# EN1190_EDP_Semester_2_Schematic.net
KiCad netlist of a schematic drawn in Altium Designer
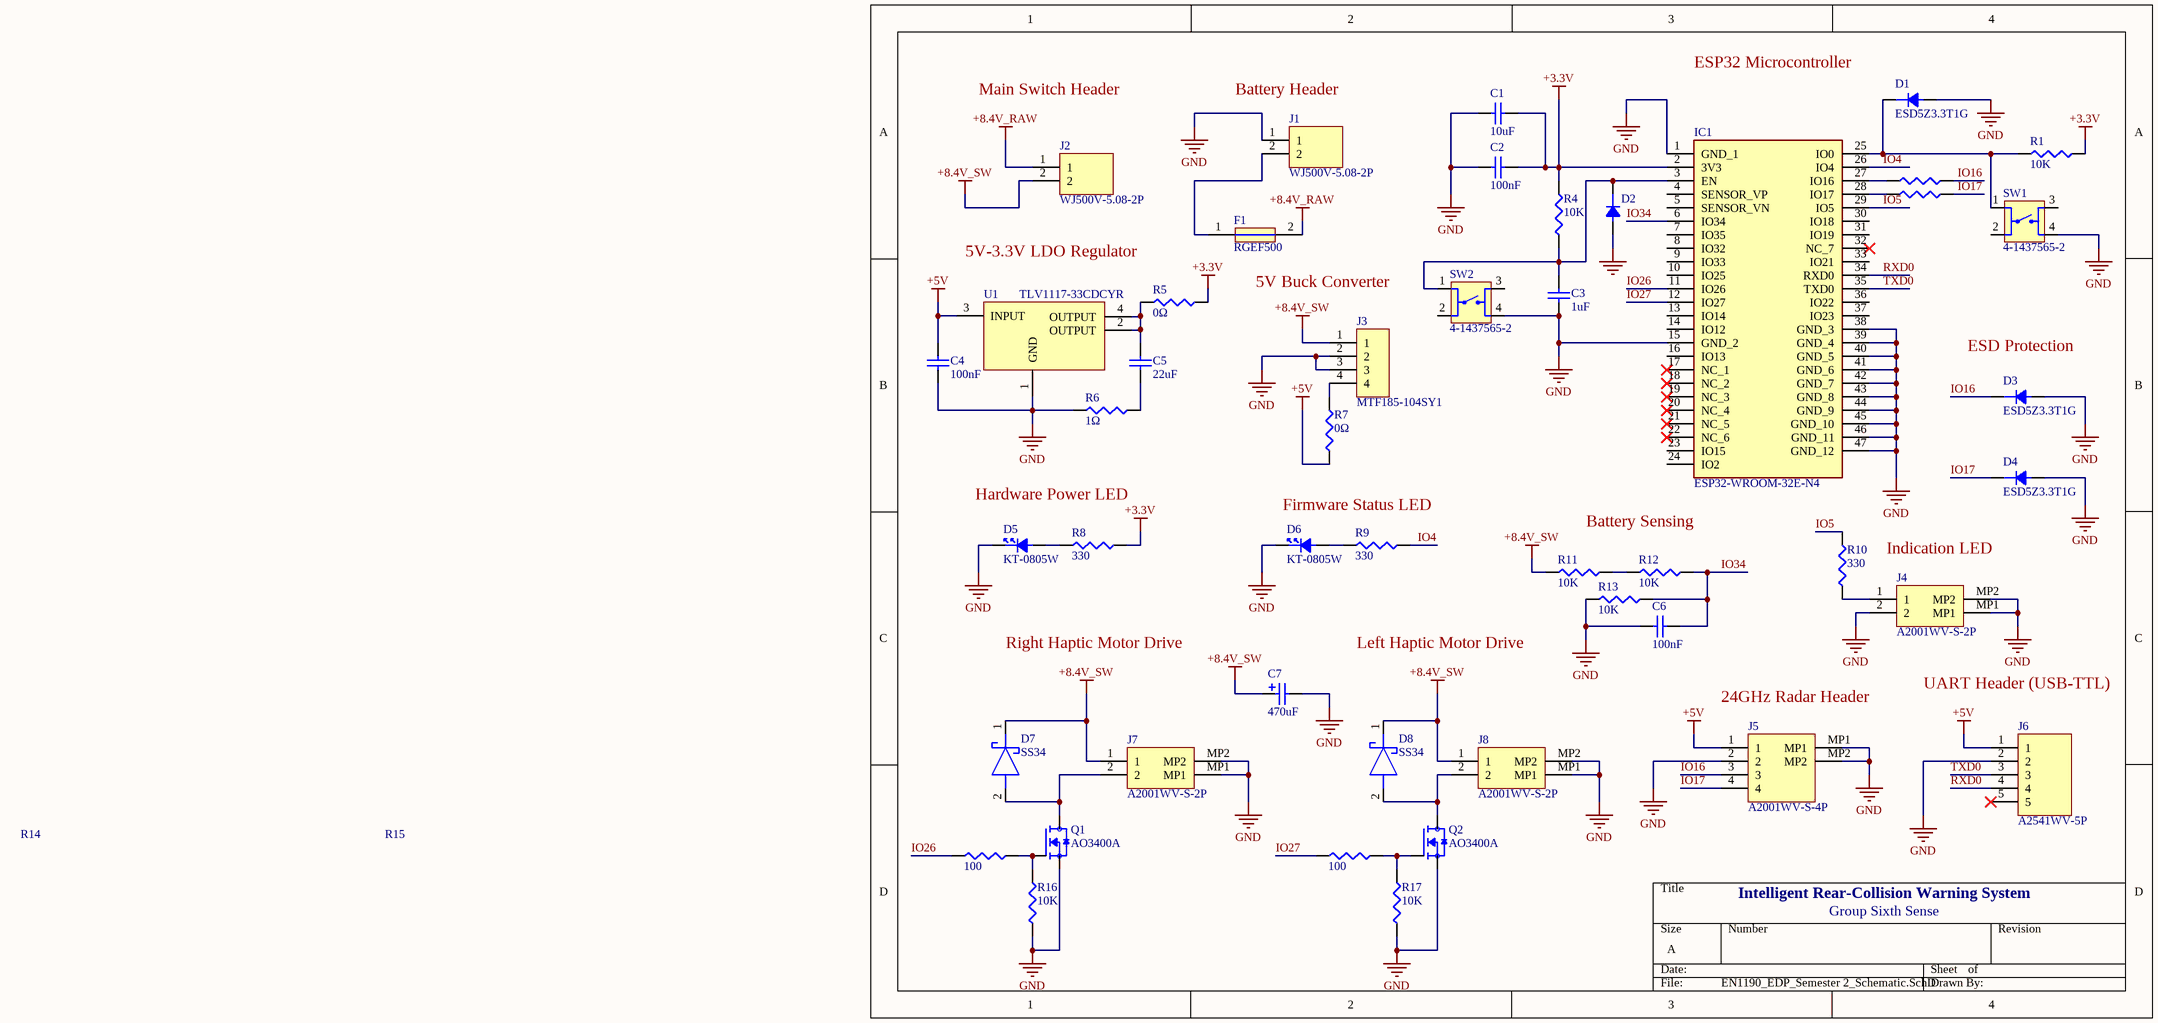
[diagram p0: EN1190_EDP_Semester 2_Schematic.SchDoc]

(export (version "E")
  (design (tool "Eeschema 10.0.6"))
  (components
    (comp (ref "C1")
      (value "10uF")
      (footprint "CAPC2012X145N")
      (description "10uF ±10% 25V Ceramic Capacitor X5R 0805")
      (fields
        (field (name "LCSC PART NUMBER") "C15850")
        (field (name "MANUFACTURER") "Samsung Electro-Mechanics")
      )
      (libsource (lib "Integrated_Library1") (part "CL21A106KAYNNNE"))
    )
    (comp (ref "C2")
      (value "100nF")
      (footprint "CAPC2012X70")
      (description "100nF ±10% 50V Ceramic Capacitor X7R 0805")
      (fields
        (field (name "MANUFACTURER") "YAGEO")
        (field (name "MANUFACTURER PART NUMBER") "CC0805KRX7R9BB104")
      )
      (libsource (lib "Integrated_Library1") (part "CC0805KRX7R9BB104"))
    )
    (comp (ref "C3")
      (value "1uF")
      (footprint "CAPC2012X135N")
      (description "1uF ±10% 50V Ceramic Capacitor X7R 0805")
      (fields
        (field (name "LCSC PART NUMBER") "C28323")
        (field (name "MANUFACTUER PART NUMBER") "CL21B105KBFNNNE")
      )
      (libsource (lib "Integrated_Library1") (part "CL21B105KBFNNNE"))
    )
    (comp (ref "C4")
      (value "100nF")
      (footprint "CAPC2012X70")
      (description "100nF ±10% 50V Ceramic Capacitor X7R 0805")
      (fields
        (field (name "MANUFACTURER") "YAGEO")
        (field (name "MANUFACTURER PART NUMBER") "CC0805KRX7R9BB104")
      )
      (libsource (lib "Integrated_Library1") (part "CC0805KRX7R9BB104"))
    )
    (comp (ref "C5")
      (value "22uF")
      (footprint "CAPC3216X180N")
      (description "22uF ±10% 16V Ceramic Capacitor X5R 1206")
      (fields (field (name "LCSC PART NUMBER") "C90146"))
      (libsource (lib "Integrated_Library1") (part "CL31A226KOHNNNE"))
    )
    (comp (ref "C6")
      (value "100nF")
      (footprint "CAPC2012X70")
      (description "100nF ±10% 50V Ceramic Capacitor X7R 0805")
      (fields
        (field (name "MANUFACTURER") "YAGEO")
        (field (name "MANUFACTURER PART NUMBER") "CC0805KRX7R9BB104")
      )
      (libsource (lib "Integrated_Library1") (part "CC0805KRX7R9BB104"))
    )
    (comp (ref "C7")
      (value "470uF")
      (footprint "CAPPRD500W60D1025H1400")
      (description "470uF 25V Aluminum Electrolytic Capacitors Through Hole,D10xL12.5mm 10000hrs@105℃")
      (fields (field (name "LCSC PART NUMBER") "C88740") (field (name "MANUFACTURER") "Rubycon"))
      (libsource (lib "Integrated_Library1") (part "25YXJ470M10X12.5"))
    )
    (comp (ref "D1")
      (value "ESD5Z3.3T1G")
      (footprint "SODFL1608X70N")
      (description "14.1VC Clamp 11.2A Ipp TVS DIODE SOD-523")
      (fields (field (name "MANUFACTURER") "onsemi") (field (name "LCSC PART NUMBER") "C61148"))
      (libsource (lib "Integrated_Library1") (part "ESD5Z3.3T1G"))
    )
    (comp (ref "D2")
      (value "ESD5Z3.3T1G")
      (footprint "SODFL1608X70N")
      (description "14.1VC Clamp 11.2A Ipp TVS DIODE SOD-523")
      (fields (field (name "MANUFACTURER") "onsemi") (field (name "LCSC PART NUMBER") "C61148"))
      (libsource (lib "Integrated_Library1") (part "ESD5Z3.3T1G"))
    )
    (comp (ref "D3")
      (value "ESD5Z3.3T1G")
      (footprint "SODFL1608X70N")
      (description "14.1VC Clamp 11.2A Ipp TVS DIODE SOD-523")
      (fields (field (name "MANUFACTURER") "onsemi") (field (name "LCSC PART NUMBER") "C61148"))
      (libsource (lib "Integrated_Library1") (part "ESD5Z3.3T1G"))
    )
    (comp (ref "D4")
      (value "ESD5Z3.3T1G")
      (footprint "SODFL1608X70N")
      (description "14.1VC Clamp 11.2A Ipp TVS DIODE SOD-523")
      (fields (field (name "MANUFACTURER") "onsemi") (field (name "LCSC PART NUMBER") "C61148"))
      (libsource (lib "Integrated_Library1") (part "ESD5Z3.3T1G"))
    )
    (comp (ref "D5")
      (value "KT-0805W")
      (footprint "LED_KT-0805W")
      (description "White LED Indication - Discrete 2.6V~3.2V 0805")
      (fields (field (name "MANUFACTURER") "Hubei KENTO Elec") (field (name "LCSC PART NUMBER") "C34499"))
      (libsource (lib "Integrated_Library1") (part "KT-0805W"))
    )
    (comp (ref "D6")
      (value "KT-0805W")
      (footprint "LED_KT-0805W")
      (description "White LED Indication - Discrete 2.6V~3.2V 0805")
      (fields (field (name "MANUFACTURER") "Hubei KENTO Elec") (field (name "LCSC PART NUMBER") "C34499"))
      (libsource (lib "Integrated_Library1") (part "KT-0805W"))
    )
    (comp (ref "D7")
      (value "SS34")
      (footprint "DIOM5127X241N")
      (description "Diode Independent 40V 3A Surface Mount SMA(DO-214AC)")
      (fields
        (field (name "LCSC PART NUMBER") "C8678")
        (field (name "MANUFACTURER") "MDD(Microdiode Semiconductor)")
      )
      (libsource (lib "Integrated_Library1") (part "SS34 SMA"))
    )
    (comp (ref "D8")
      (value "SS34")
      (footprint "DIOM5127X241N")
      (description "Diode Independent 40V 3A Surface Mount SMA(DO-214AC)")
      (fields
        (field (name "LCSC PART NUMBER") "C8678")
        (field (name "MANUFACTURER") "MDD(Microdiode Semiconductor)")
      )
      (libsource (lib "Integrated_Library1") (part "SS34 SMA"))
    )
    (comp (ref "F1")
      (value "RGEF500")
      (footprint "RGEF500")
      (description "Polymeric PTC Resettable Fuse 16V 5A Through Hole P=5.08mm")
      (fields (field (name "MANUFACTURER") "Littelfuse") (field (name "LCSC PART NUMBER") "C468988"))
      (libsource (lib "Integrated_Library1") (part "RGEF500"))
    )
    (comp (ref "IC1")
      (value "ESP32-WROOM-32E-N4")
      (footprint "ESP32WROOM32EN4")
      (description "2.4GHz On-board PCB Antenna -98dBm SMD,25.5x18mm RF Transceiver Modules and Modems RoHS")
      (fields
        (field (name "MOUSER PART NUMBER") "356-ESP32WRM32E132PH")
        (field (name "LCSC PART NUMBER") "C701341")
      )
      (libsource (lib "Schlib3") (part "ESP32-WROOM-32E-N4"))
    )
    (comp (ref "J1")
      (value "WJ500V-5.08-2P")
      (footprint "WJ500V5082P")
      (description "2 Position Wire to Board Terminal Block Through Hole 5.08mm")
      (fields (field (name "LCSC PART NUMBER") "C8465"))
      (libsource (lib "Schlib3") (part "WJ500V-5.08-2P"))
    )
    (comp (ref "J2")
      (value "WJ500V-5.08-2P")
      (footprint "WJ500V5082P")
      (description "2 Position Wire to Board Terminal Block Through Hole 5.08mm")
      (fields (field (name "LCSC PART NUMBER") "C8465"))
      (libsource (lib "Schlib3") (part "WJ500V-5.08-2P"))
    )
    (comp (ref "J3")
      (value "MTF185-104SY1")
      (footprint "RHDR4W64P0X254_1X4_1041X250X865P")
      (description "Female Header 4 Position 2.54mm Pitch Single Row Through Hole")
      (fields (field (name "LCSC PART NUMBER") "C358718") (field (name "MANUFACTURER") "Mintron"))
      (libsource (lib "Integrated_Library1") (part "MTF185-104SY1"))
    )
    (comp (ref "J4")
      (value "A2001WV-S-2P")
      (footprint "A2001WVS2P")
      (description "Connector Header 2 position 2mm Pitch")
      (fields (field (name "LCSC PART NUMBER") "C225226"))
      (libsource (lib "Integrated_Library1") (part "A2001WV-S-2P"))
    )
    (comp (ref "J5")
      (value "A2001WV-S-4P")
      (footprint "A2001WVS4P")
      (description "Connector Header 4 position 2mm Pitch")
      (fields (field (name "LCSC PART NUMBER") "C225228"))
      (libsource (lib "Integrated_Library1") (part "A2001WV-S-4P"))
    )
    (comp (ref "J6")
      (value "A2541WV-5P")
      (footprint "HDRV5W64P0X254_1X5_1270X254X899P")
      (description "Pin Header 5 Position 2.54mm Pitch Single Row Through Hole -40℃~+105℃")
      (fields (field (name "LCSC PART NUMBER") "C225480"))
      (libsource (lib "Integrated_Library1") (part "A2541WV-5P"))
    )
    (comp (ref "J7")
      (value "A2001WV-S-2P")
      (footprint "A2001WVS2P")
      (description "Connector Header 2 position 2mm Pitch")
      (fields (field (name "LCSC PART NUMBER") "C225226"))
      (libsource (lib "Integrated_Library1") (part "A2001WV-S-2P"))
    )
    (comp (ref "J8")
      (value "A2001WV-S-2P")
      (footprint "A2001WVS2P")
      (description "Connector Header 2 position 2mm Pitch")
      (fields (field (name "LCSC PART NUMBER") "C225226"))
      (libsource (lib "Integrated_Library1") (part "A2001WV-S-2P"))
    )
    (comp (ref "Q1")
      (value "AO3400A")
      (footprint "SOT95P280X125-3N")
      (description "N-Channel 30 V 5.7A (Ta) 1.4W (Ta) Surface Mount SOT-23-3")
      (fields (field (name "MF") "Alpha & Omega Semiconductor") (field (name "LCSC PART NUMBER") "C20917"))
      (libsource (lib "Integrated_Library1") (part "AO3400A"))
    )
    (comp (ref "Q2")
      (value "AO3400A")
      (footprint "SOT95P280X125-3N")
      (description "N-Channel 30 V 5.7A (Ta) 1.4W (Ta) Surface Mount SOT-23-3")
      (fields (field (name "MF") "Alpha & Omega Semiconductor") (field (name "LCSC PART NUMBER") "C20917"))
      (libsource (lib "Integrated_Library1") (part "AO3400A"))
    )
    (comp (ref "R1")
      (value "10K")
      (footprint "RESC2012X65N")
      (description "10kΩ ±1% 125mW 0805 Thick Film Resistor")
      (fields
        (field (name "LCSC PART NUMBER") "C17414")
        (field (name "MANUFACTUER PART NUMBER") "0805W8F1002T5E")
      )
      (libsource (lib "Integrated_Library1") (part "0805W8F1002T5E"))
    )
    (comp (ref "R2")
      (value "0Ω")
      (footprint "RESC2012X65N")
      (description "0Ω ±1% 125mW 0805 Thick Film Resistor")
      (fields
        (field (name "MANUFACTURER") "UNI-ROYAL")
        (field (name "MANUFACTURER PART NUMBER") "0805W8F0000T5E")
      )
      (libsource (lib "Integrated_Library1") (part "0805W8F0000T5E"))
    )
    (comp (ref "R3")
      (value "0Ω")
      (footprint "RESC2012X65N")
      (description "0Ω ±1% 125mW 0805 Thick Film Resistor")
      (fields
        (field (name "MANUFACTURER") "UNI-ROYAL")
        (field (name "MANUFACTURER PART NUMBER") "0805W8F0000T5E")
      )
      (libsource (lib "Integrated_Library1") (part "0805W8F0000T5E"))
    )
    (comp (ref "R4")
      (value "10K")
      (footprint "RESC2012X65N")
      (description "10kΩ ±1% 125mW 0805 Thick Film Resistor")
      (fields
        (field (name "LCSC PART NUMBER") "C17414")
        (field (name "MANUFACTUER PART NUMBER") "0805W8F1002T5E")
      )
      (libsource (lib "Integrated_Library1") (part "0805W8F1002T5E"))
    )
    (comp (ref "R5")
      (value "0Ω")
      (footprint "RESC2012X65N")
      (description "0Ω ±1% 125mW 0805 Thick Film Resistor")
      (fields
        (field (name "MANUFACTURER") "UNI-ROYAL")
        (field (name "MANUFACTURER PART NUMBER") "0805W8F0000T5E")
      )
      (libsource (lib "Integrated_Library1") (part "0805W8F0000T5E"))
    )
    (comp (ref "R6")
      (value "1Ω")
      (footprint "RESC2012X65N")
      (description "1Ω ±1% 125mW 0805 Thick Film Resistor")
      (fields
        (field (name "MANUFACTURER") "UNI-ROYAL")
        (field (name "MANUFACTURER PART NUMBER") "0805W8F100KT5E")
      )
      (libsource (lib "Integrated_Library1") (part "0805W8F100KT5E"))
    )
    (comp (ref "R7")
      (value "0Ω")
      (footprint "RESC2012X65N")
      (description "0Ω ±1% 125mW 0805 Thick Film Resistor")
      (fields
        (field (name "MANUFACTURER") "UNI-ROYAL")
        (field (name "MANUFACTURER PART NUMBER") "0805W8F0000T5E")
      )
      (libsource (lib "Integrated_Library1") (part "0805W8F0000T5E"))
    )
    (comp (ref "R8")
      (value "330")
      (footprint "RESC2012X65N")
      (description "330Ω ±1% 125mW 0805 Thick Film Resistor")
      (fields
        (field (name "MANUFACTURER") "UNI-ROYAL")
        (field (name "MANUFACTURER PART NUMBER") "0805W8F3300T5E")
      )
      (libsource (lib "Integrated_Library1") (part "0805W8F3300T5E"))
    )
    (comp (ref "R9")
      (value "330")
      (footprint "RESC2012X65N")
      (description "330Ω ±1% 125mW 0805 Thick Film Resistor")
      (fields
        (field (name "MANUFACTURER") "UNI-ROYAL")
        (field (name "MANUFACTURER PART NUMBER") "0805W8F3300T5E")
      )
      (libsource (lib "Integrated_Library1") (part "0805W8F3300T5E"))
    )
    (comp (ref "R10")
      (value "330")
      (footprint "RESC2012X65N")
      (description "330Ω ±1% 125mW 0805 Thick Film Resistor")
      (fields
        (field (name "MANUFACTURER") "UNI-ROYAL")
        (field (name "MANUFACTURER PART NUMBER") "0805W8F3300T5E")
      )
      (libsource (lib "Integrated_Library1") (part "0805W8F3300T5E"))
    )
    (comp (ref "R11")
      (value "10K")
      (footprint "RESC2012X65N")
      (description "10kΩ ±1% 125mW 0805 Thick Film Resistor")
      (fields
        (field (name "LCSC PART NUMBER") "C17414")
        (field (name "MANUFACTUER PART NUMBER") "0805W8F1002T5E")
      )
      (libsource (lib "Integrated_Library1") (part "0805W8F1002T5E"))
    )
    (comp (ref "R12")
      (value "10K")
      (footprint "RESC2012X65N")
      (description "10kΩ ±1% 125mW 0805 Thick Film Resistor")
      (fields
        (field (name "LCSC PART NUMBER") "C17414")
        (field (name "MANUFACTUER PART NUMBER") "0805W8F1002T5E")
      )
      (libsource (lib "Integrated_Library1") (part "0805W8F1002T5E"))
    )
    (comp (ref "R13")
      (value "10K")
      (footprint "RESC2012X65N")
      (description "10kΩ ±1% 125mW 0805 Thick Film Resistor")
      (fields
        (field (name "LCSC PART NUMBER") "C17414")
        (field (name "MANUFACTUER PART NUMBER") "0805W8F1002T5E")
      )
      (libsource (lib "Integrated_Library1") (part "0805W8F1002T5E"))
    )
    (comp (ref "R14")
      (value "100")
      (footprint "RESC2012X65N - duplicate")
      (description "100Ω ±1% 125mW 0805 Thick Film Resistor")
      (fields
        (field (name "LCSC PART NUMBER") "C17408")
        (field (name "MANUFACTURER PART NUMBER") "0805W8F1000T5E")
      )
      (libsource (lib "Integrated_Library1") (part "0805W8F1000T5E"))
    )
    (comp (ref "R15")
      (value "100")
      (footprint "RESC2012X65N - duplicate")
      (description "100Ω ±1% 125mW 0805 Thick Film Resistor")
      (fields
        (field (name "LCSC PART NUMBER") "C17408")
        (field (name "MANUFACTURER PART NUMBER") "0805W8F1000T5E")
      )
      (libsource (lib "Integrated_Library1") (part "0805W8F1000T5E"))
    )
    (comp (ref "R16")
      (value "10K")
      (footprint "RESC2012X65N")
      (description "10kΩ ±1% 125mW 0805 Thick Film Resistor")
      (fields
        (field (name "LCSC PART NUMBER") "C17414")
        (field (name "MANUFACTUER PART NUMBER") "0805W8F1002T5E")
      )
      (libsource (lib "Integrated_Library1") (part "0805W8F1002T5E"))
    )
    (comp (ref "R17")
      (value "10K")
      (footprint "RESC2012X65N")
      (description "10kΩ ±1% 125mW 0805 Thick Film Resistor")
      (fields
        (field (name "LCSC PART NUMBER") "C17414")
        (field (name "MANUFACTUER PART NUMBER") "0805W8F1002T5E")
      )
      (libsource (lib "Integrated_Library1") (part "0805W8F1002T5E"))
    )
    (comp (ref "SW1")
      (value "4-1437565-2")
      (footprint "SW_4-1437565-2")
      (description "Switch Tactile OFF (ON) SPST Round Button Gull Wing 0.05A 24VDC 1VA 9.18N SMD T/R")
      (fields (field (name "MF") "TE Connectivity") (field (name "MP") "FSM4JSMATR"))
      (libsource (lib "Integrated_Library1") (part "4-1437565-2"))
    )
    (comp (ref "SW2")
      (value "4-1437565-2")
      (footprint "SW_4-1437565-2")
      (description "Switch Tactile OFF (ON) SPST Round Button Gull Wing 0.05A 24VDC 1VA 9.18N SMD T/R")
      (fields (field (name "MF") "TE Connectivity") (field (name "MP") "FSM4JSMATR"))
      (libsource (lib "Integrated_Library1") (part "4-1437565-2"))
    )
    (comp (ref "U1")
      (value "TLV1117-33CDCYR")
      (footprint "SOT230P700X180-4N")
      (description "3.3V 15V Positive Fixed SOT-223 Voltage Regulators - Linear, Low Drop Out (LDO) Regulators RoHS")
      (fields (field (name "LCSC PART NUMBER") "C91728"))
      (libsource (lib "Integrated_Library1") (part "TLV1117-33CDCYR"))
    )
  )
  (nets
    (net (code "1") (name "+3.3V") (class "Default")
      (node (ref "C1") (pin "2") (pinfunction "2_2") (pintype "passive"))
      (node (ref "C2") (pin "1") (pinfunction "1_1") (pintype "passive"))
      (node (ref "IC1") (pin "2") (pinfunction "3V3_2") (pintype "passive"))
      (node (ref "R1") (pin "2") (pinfunction "2_2") (pintype "passive"))
      (node (ref "R4") (pin "1") (pinfunction "1_1") (pintype "passive"))
      (node (ref "R5") (pin "2") (pinfunction "2_2") (pintype "passive"))
      (node (ref "R8") (pin "2") (pinfunction "2_2") (pintype "passive"))
    )
    (net (code "2") (name "+5V") (class "Default")
      (node (ref "C4") (pin "2") (pinfunction "2_2") (pintype "passive"))
      (node (ref "J5") (pin "1") (pinfunction "1_1") (pintype "passive"))
      (node (ref "J6") (pin "1") (pinfunction "1_1") (pintype "passive"))
      (node (ref "R7") (pin "1") (pinfunction "1_1") (pintype "passive"))
      (node (ref "U1") (pin "3") (pinfunction "INPUT_3") (pintype "power_in"))
    )
    (net (code "3") (name "+8.4V_RAW") (class "Default")
      (node (ref "F1") (pin "2") (pinfunction "2_2") (pintype "passive"))
      (node (ref "J2") (pin "1") (pinfunction "1_1") (pintype "passive"))
    )
    (net (code "4") (name "+8.4V_SW") (class "Default")
      (node (ref "C7") (pin "1") (pinfunction "1_1") (pintype "passive"))
      (node (ref "D7") (pin "1") (pinfunction "K_1") (pintype "passive"))
      (node (ref "D8") (pin "1") (pinfunction "K_1") (pintype "passive"))
      (node (ref "J2") (pin "2") (pinfunction "2_2") (pintype "passive"))
      (node (ref "J3") (pin "1") (pinfunction "1_1") (pintype "passive"))
      (node (ref "J7") (pin "1") (pinfunction "1_1") (pintype "passive"))
      (node (ref "J8") (pin "1") (pinfunction "1_1") (pintype "passive"))
      (node (ref "R11") (pin "2") (pinfunction "2_2") (pintype "passive"))
    )
    (net (code "5") (name "/IO4") (class "Default")
      (node (ref "IC1") (pin "26") (pinfunction "IO4_26") (pintype "passive"))
      (node (ref "R9") (pin "2") (pinfunction "2_2") (pintype "passive"))
    )
    (net (code "6") (name "/IO5") (class "Default")
      (node (ref "IC1") (pin "29") (pinfunction "IO5_29") (pintype "passive"))
      (node (ref "R10") (pin "2") (pinfunction "2_2") (pintype "passive"))
    )
    (net (code "7") (name "/IO16") (class "Default")
      (node (ref "D3") (pin "1") (pinfunction "1_1") (pintype "passive"))
      (node (ref "J5") (pin "3") (pinfunction "3_3") (pintype "passive"))
      (node (ref "R2") (pin "2") (pinfunction "2_2") (pintype "passive"))
    )
    (net (code "8") (name "/IO17") (class "Default")
      (node (ref "D4") (pin "1") (pinfunction "1_1") (pintype "passive"))
      (node (ref "J5") (pin "4") (pinfunction "4_4") (pintype "passive"))
      (node (ref "R3") (pin "2") (pinfunction "2_2") (pintype "passive"))
    )
    (net (code "9") (name "/IO26") (class "Default")
      (node (ref "IC1") (pin "11") (pinfunction "IO26_11") (pintype "passive"))
      (node (ref "R14") (pin "1") (pinfunction "1_1") (pintype "passive"))
    )
    (net (code "10") (name "/IO27") (class "Default")
      (node (ref "IC1") (pin "12") (pinfunction "IO27_12") (pintype "passive"))
      (node (ref "R15") (pin "1") (pinfunction "1_1") (pintype "passive"))
    )
    (net (code "11") (name "/IO34") (class "Default")
      (node (ref "C6") (pin "2") (pinfunction "2_2") (pintype "passive"))
      (node (ref "IC1") (pin "6") (pinfunction "IO34_6") (pintype "passive"))
      (node (ref "R12") (pin "1") (pinfunction "1_1") (pintype "passive"))
      (node (ref "R13") (pin "2") (pinfunction "2_2") (pintype "passive"))
    )
    (net (code "12") (name "/RXD0") (class "Default")
      (node (ref "IC1") (pin "34") (pinfunction "RXD0_34") (pintype "passive"))
      (node (ref "J6") (pin "4") (pinfunction "4_4") (pintype "passive"))
    )
    (net (code "13") (name "/TXD0") (class "Default")
      (node (ref "IC1") (pin "35") (pinfunction "TXD0_35") (pintype "passive"))
      (node (ref "J6") (pin "3") (pinfunction "3_3") (pintype "passive"))
    )
    (net (code "14") (name "GND") (class "Default")
      (node (ref "C1") (pin "1") (pinfunction "1_1") (pintype "passive"))
      (node (ref "C2") (pin "2") (pinfunction "2_2") (pintype "passive"))
      (node (ref "C3") (pin "1") (pinfunction "1_1") (pintype "passive"))
      (node (ref "C4") (pin "1") (pinfunction "1_1") (pintype "passive"))
      (node (ref "C6") (pin "1") (pinfunction "1_1") (pintype "passive"))
      (node (ref "C7") (pin "2") (pinfunction "2_2") (pintype "passive"))
      (node (ref "D1") (pin "2") (pinfunction "2_2") (pintype "passive"))
      (node (ref "D2") (pin "2") (pinfunction "2_2") (pintype "passive"))
      (node (ref "D3") (pin "2") (pinfunction "2_2") (pintype "passive"))
      (node (ref "D4") (pin "2") (pinfunction "2_2") (pintype "passive"))
      (node (ref "D5") (pin "1") (pinfunction "1_1") (pintype "passive"))
      (node (ref "D6") (pin "1") (pinfunction "1_1") (pintype "passive"))
      (node (ref "IC1") (pin "1") (pinfunction "GND_1_1") (pintype "passive"))
      (node (ref "IC1") (pin "15") (pinfunction "GND_2_15") (pintype "passive"))
      (node (ref "IC1") (pin "38") (pinfunction "GND_3_38") (pintype "passive"))
      (node (ref "IC1") (pin "39") (pinfunction "GND_4_39") (pintype "passive"))
      (node (ref "IC1") (pin "40") (pinfunction "GND_5_40") (pintype "passive"))
      (node (ref "IC1") (pin "41") (pinfunction "GND_6_41") (pintype "passive"))
      (node (ref "IC1") (pin "42") (pinfunction "GND_7_42") (pintype "passive"))
      (node (ref "IC1") (pin "43") (pinfunction "GND_8_43") (pintype "passive"))
      (node (ref "IC1") (pin "44") (pinfunction "GND_9_44") (pintype "passive"))
      (node (ref "IC1") (pin "45") (pinfunction "GND_10_45") (pintype "passive"))
      (node (ref "IC1") (pin "46") (pinfunction "GND_11_46") (pintype "passive"))
      (node (ref "IC1") (pin "47") (pinfunction "GND_12_47") (pintype "passive"))
      (node (ref "J1") (pin "1") (pinfunction "1_1") (pintype "passive"))
      (node (ref "J3") (pin "2") (pinfunction "2_2") (pintype "passive"))
      (node (ref "J3") (pin "3") (pinfunction "3_3") (pintype "passive"))
      (node (ref "J4") (pin "2") (pinfunction "2_2") (pintype "passive"))
      (node (ref "J4") (pin "MP1") (pinfunction "MP1_MP1") (pintype "passive"))
      (node (ref "J4") (pin "MP2") (pinfunction "MP2_MP2") (pintype "passive"))
      (node (ref "J5") (pin "2") (pinfunction "2_2") (pintype "passive"))
      (node (ref "J5") (pin "MP1") (pinfunction "MP1_MP1") (pintype "passive"))
      (node (ref "J5") (pin "MP2") (pinfunction "MP2_MP2") (pintype "passive"))
      (node (ref "J6") (pin "2") (pinfunction "2_2") (pintype "passive"))
      (node (ref "J7") (pin "MP1") (pinfunction "MP1_MP1") (pintype "passive"))
      (node (ref "J7") (pin "MP2") (pinfunction "MP2_MP2") (pintype "passive"))
      (node (ref "J8") (pin "MP1") (pinfunction "MP1_MP1") (pintype "passive"))
      (node (ref "J8") (pin "MP2") (pinfunction "MP2_MP2") (pintype "passive"))
      (node (ref "Q1") (pin "2") (pinfunction "S_2") (pintype "passive"))
      (node (ref "Q2") (pin "2") (pinfunction "S_2") (pintype "passive"))
      (node (ref "R13") (pin "1") (pinfunction "1_1") (pintype "passive"))
      (node (ref "R16") (pin "2") (pinfunction "2_2") (pintype "passive"))
      (node (ref "R17") (pin "2") (pinfunction "2_2") (pintype "passive"))
      (node (ref "R6") (pin "2") (pinfunction "2_2") (pintype "passive"))
      (node (ref "SW1") (pin "4") (pinfunction "4_4") (pintype "passive"))
      (node (ref "SW2") (pin "4") (pinfunction "4_4") (pintype "passive"))
      (node (ref "U1") (pin "1") (pinfunction "GND_1") (pintype "power_in"))
    )
    (net (code "15") (name "Net-(C5-Pad1)") (class "Default")
      (node (ref "C5") (pin "1") (pinfunction "1_1") (pintype "passive"))
      (node (ref "R6") (pin "1") (pinfunction "1_1") (pintype "passive"))
    )
    (net (code "16") (name "Net-(C5-Pad2)") (class "Default")
      (node (ref "C5") (pin "2") (pinfunction "2_2") (pintype "passive"))
      (node (ref "R5") (pin "1") (pinfunction "1_1") (pintype "passive"))
      (node (ref "U1") (pin "2") (pinfunction "OUTPUT_2") (pintype "power_in"))
      (node (ref "U1") (pin "4") (pinfunction "OUTPUT_4") (pintype "power_in"))
    )
    (net (code "17") (name "Net-(D5-Pad2)") (class "Default")
      (node (ref "D5") (pin "2") (pinfunction "2_2") (pintype "passive"))
      (node (ref "R8") (pin "1") (pinfunction "1_1") (pintype "passive"))
    )
    (net (code "18") (name "Net-(D6-Pad2)") (class "Default")
      (node (ref "D6") (pin "2") (pinfunction "2_2") (pintype "passive"))
      (node (ref "R9") (pin "1") (pinfunction "1_1") (pintype "passive"))
    )
    (net (code "19") (name "Net-(D7-A)") (class "Default")
      (node (ref "D7") (pin "2") (pinfunction "A_2") (pintype "passive"))
      (node (ref "J7") (pin "2") (pinfunction "2_2") (pintype "passive"))
      (node (ref "Q1") (pin "3") (pinfunction "D_3") (pintype "passive"))
    )
    (net (code "20") (name "Net-(D8-A)") (class "Default")
      (node (ref "D8") (pin "2") (pinfunction "A_2") (pintype "passive"))
      (node (ref "J8") (pin "2") (pinfunction "2_2") (pintype "passive"))
      (node (ref "Q2") (pin "3") (pinfunction "D_3") (pintype "passive"))
    )
    (net (code "21") (name "Net-(F1-Pad1)") (class "Default")
      (node (ref "F1") (pin "1") (pinfunction "1_1") (pintype "passive"))
      (node (ref "J1") (pin "2") (pinfunction "2_2") (pintype "passive"))
    )
    (net (code "22") (name "Net-(IC1-EN)") (class "Default")
      (node (ref "C3") (pin "2") (pinfunction "2_2") (pintype "passive"))
      (node (ref "D2") (pin "1") (pinfunction "1_1") (pintype "passive"))
      (node (ref "IC1") (pin "3") (pinfunction "EN_3") (pintype "passive"))
      (node (ref "R4") (pin "2") (pinfunction "2_2") (pintype "passive"))
      (node (ref "SW2") (pin "1") (pinfunction "1_1") (pintype "passive"))
    )
    (net (code "23") (name "Net-(IC1-IO0)") (class "Default")
      (node (ref "D1") (pin "1") (pinfunction "1_1") (pintype "passive"))
      (node (ref "IC1") (pin "25") (pinfunction "IO0_25") (pintype "passive"))
      (node (ref "R1") (pin "1") (pinfunction "1_1") (pintype "passive"))
      (node (ref "SW1") (pin "1") (pinfunction "1_1") (pintype "passive"))
    )
    (net (code "24") (name "Net-(IC1-IO16)") (class "Default")
      (node (ref "IC1") (pin "27") (pinfunction "IO16_27") (pintype "passive"))
      (node (ref "R2") (pin "1") (pinfunction "1_1") (pintype "passive"))
    )
    (net (code "25") (name "Net-(IC1-IO17)") (class "Default")
      (node (ref "IC1") (pin "28") (pinfunction "IO17_28") (pintype "passive"))
      (node (ref "R3") (pin "1") (pinfunction "1_1") (pintype "passive"))
    )
    (net (code "26") (name "Net-(J3-Pad4)") (class "Default")
      (node (ref "J3") (pin "4") (pinfunction "4_4") (pintype "passive"))
      (node (ref "R7") (pin "2") (pinfunction "2_2") (pintype "passive"))
    )
    (net (code "27") (name "Net-(J4-Pad1)") (class "Default")
      (node (ref "J4") (pin "1") (pinfunction "1_1") (pintype "passive"))
      (node (ref "R10") (pin "1") (pinfunction "1_1") (pintype "passive"))
    )
    (net (code "28") (name "Net-(Q1-G)") (class "Default")
      (node (ref "Q1") (pin "1") (pinfunction "G_1") (pintype "passive"))
      (node (ref "R14") (pin "2") (pinfunction "2_2") (pintype "passive"))
      (node (ref "R16") (pin "1") (pinfunction "1_1") (pintype "passive"))
    )
    (net (code "29") (name "Net-(Q2-G)") (class "Default")
      (node (ref "Q2") (pin "1") (pinfunction "G_1") (pintype "passive"))
      (node (ref "R15") (pin "2") (pinfunction "2_2") (pintype "passive"))
      (node (ref "R17") (pin "1") (pinfunction "1_1") (pintype "passive"))
    )
    (net (code "30") (name "Net-(R11-Pad1)") (class "Default")
      (node (ref "R11") (pin "1") (pinfunction "1_1") (pintype "passive"))
      (node (ref "R12") (pin "2") (pinfunction "2_2") (pintype "passive"))
    )
    (net (code "31") (name "unconnected-(IC1-IO2-Pad24)") (class "Default")
      (node (ref "IC1") (pin "24") (pinfunction "IO2_24") (pintype "passive"))
    )
    (net (code "32") (name "unconnected-(IC1-IO12-Pad14)") (class "Default")
      (node (ref "IC1") (pin "14") (pinfunction "IO12_14") (pintype "passive"))
    )
    (net (code "33") (name "unconnected-(IC1-IO13-Pad16)") (class "Default")
      (node (ref "IC1") (pin "16") (pinfunction "IO13_16") (pintype "passive"))
    )
    (net (code "34") (name "unconnected-(IC1-IO14-Pad13)") (class "Default")
      (node (ref "IC1") (pin "13") (pinfunction "IO14_13") (pintype "passive"))
    )
    (net (code "35") (name "unconnected-(IC1-IO15-Pad23)") (class "Default")
      (node (ref "IC1") (pin "23") (pinfunction "IO15_23") (pintype "passive"))
    )
    (net (code "36") (name "unconnected-(IC1-IO18-Pad30)") (class "Default")
      (node (ref "IC1") (pin "30") (pinfunction "IO18_30") (pintype "passive"))
    )
    (net (code "37") (name "unconnected-(IC1-IO19-Pad31)") (class "Default")
      (node (ref "IC1") (pin "31") (pinfunction "IO19_31") (pintype "passive"))
    )
    (net (code "38") (name "unconnected-(IC1-IO21-Pad33)") (class "Default")
      (node (ref "IC1") (pin "33") (pinfunction "IO21_33") (pintype "passive"))
    )
    (net (code "39") (name "unconnected-(IC1-IO22-Pad36)") (class "Default")
      (node (ref "IC1") (pin "36") (pinfunction "IO22_36") (pintype "passive"))
    )
    (net (code "40") (name "unconnected-(IC1-IO23-Pad37)") (class "Default")
      (node (ref "IC1") (pin "37") (pinfunction "IO23_37") (pintype "passive"))
    )
    (net (code "41") (name "unconnected-(IC1-IO25-Pad10)") (class "Default")
      (node (ref "IC1") (pin "10") (pinfunction "IO25_10") (pintype "passive"))
    )
    (net (code "42") (name "unconnected-(IC1-IO32-Pad8)") (class "Default")
      (node (ref "IC1") (pin "8") (pinfunction "IO32_8") (pintype "passive"))
    )
    (net (code "43") (name "unconnected-(IC1-IO33-Pad9)") (class "Default")
      (node (ref "IC1") (pin "9") (pinfunction "IO33_9") (pintype "passive"))
    )
    (net (code "44") (name "unconnected-(IC1-IO35-Pad7)") (class "Default")
      (node (ref "IC1") (pin "7") (pinfunction "IO35_7") (pintype "passive"))
    )
    (net (code "45") (name "unconnected-(IC1-NC_1-Pad17)") (class "Default")
      (node (ref "IC1") (pin "17") (pinfunction "NC_1_17") (pintype "passive+no_connect"))
    )
    (net (code "46") (name "unconnected-(IC1-NC_2-Pad18)") (class "Default")
      (node (ref "IC1") (pin "18") (pinfunction "NC_2_18") (pintype "passive+no_connect"))
    )
    (net (code "47") (name "unconnected-(IC1-NC_3-Pad19)") (class "Default")
      (node (ref "IC1") (pin "19") (pinfunction "NC_3_19") (pintype "passive+no_connect"))
    )
    (net (code "48") (name "unconnected-(IC1-NC_4-Pad20)") (class "Default")
      (node (ref "IC1") (pin "20") (pinfunction "NC_4_20") (pintype "passive+no_connect"))
    )
    (net (code "49") (name "unconnected-(IC1-NC_5-Pad21)") (class "Default")
      (node (ref "IC1") (pin "21") (pinfunction "NC_5_21") (pintype "passive+no_connect"))
    )
    (net (code "50") (name "unconnected-(IC1-NC_6-Pad22)") (class "Default")
      (node (ref "IC1") (pin "22") (pinfunction "NC_6_22") (pintype "passive+no_connect"))
    )
    (net (code "51") (name "unconnected-(IC1-NC_7-Pad32)") (class "Default")
      (node (ref "IC1") (pin "32") (pinfunction "NC_7_32") (pintype "passive+no_connect"))
    )
    (net (code "52") (name "unconnected-(IC1-SENSOR_VN-Pad5)") (class "Default")
      (node (ref "IC1") (pin "5") (pinfunction "SENSOR_VN_5") (pintype "passive"))
    )
    (net (code "53") (name "unconnected-(IC1-SENSOR_VP-Pad4)") (class "Default")
      (node (ref "IC1") (pin "4") (pinfunction "SENSOR_VP_4") (pintype "passive"))
    )
    (net (code "54") (name "unconnected-(J6-Pad5)") (class "Default")
      (node (ref "J6") (pin "5") (pinfunction "5_5") (pintype "passive+no_connect"))
    )
    (net (code "55") (name "unconnected-(SW1-Pad2)") (class "Default")
      (node (ref "SW1") (pin "2") (pinfunction "2_2") (pintype "passive"))
    )
    (net (code "56") (name "unconnected-(SW1-Pad3)") (class "Default")
      (node (ref "SW1") (pin "3") (pinfunction "3_3") (pintype "passive"))
    )
    (net (code "57") (name "unconnected-(SW2-Pad2)") (class "Default")
      (node (ref "SW2") (pin "2") (pinfunction "2_2") (pintype "passive"))
    )
    (net (code "58") (name "unconnected-(SW2-Pad3)") (class "Default")
      (node (ref "SW2") (pin "3") (pinfunction "3_3") (pintype "passive"))
    )
  )
)
